# Side_Panel_f1.net
KiCad netlist of a schematic drawn in EAGLE
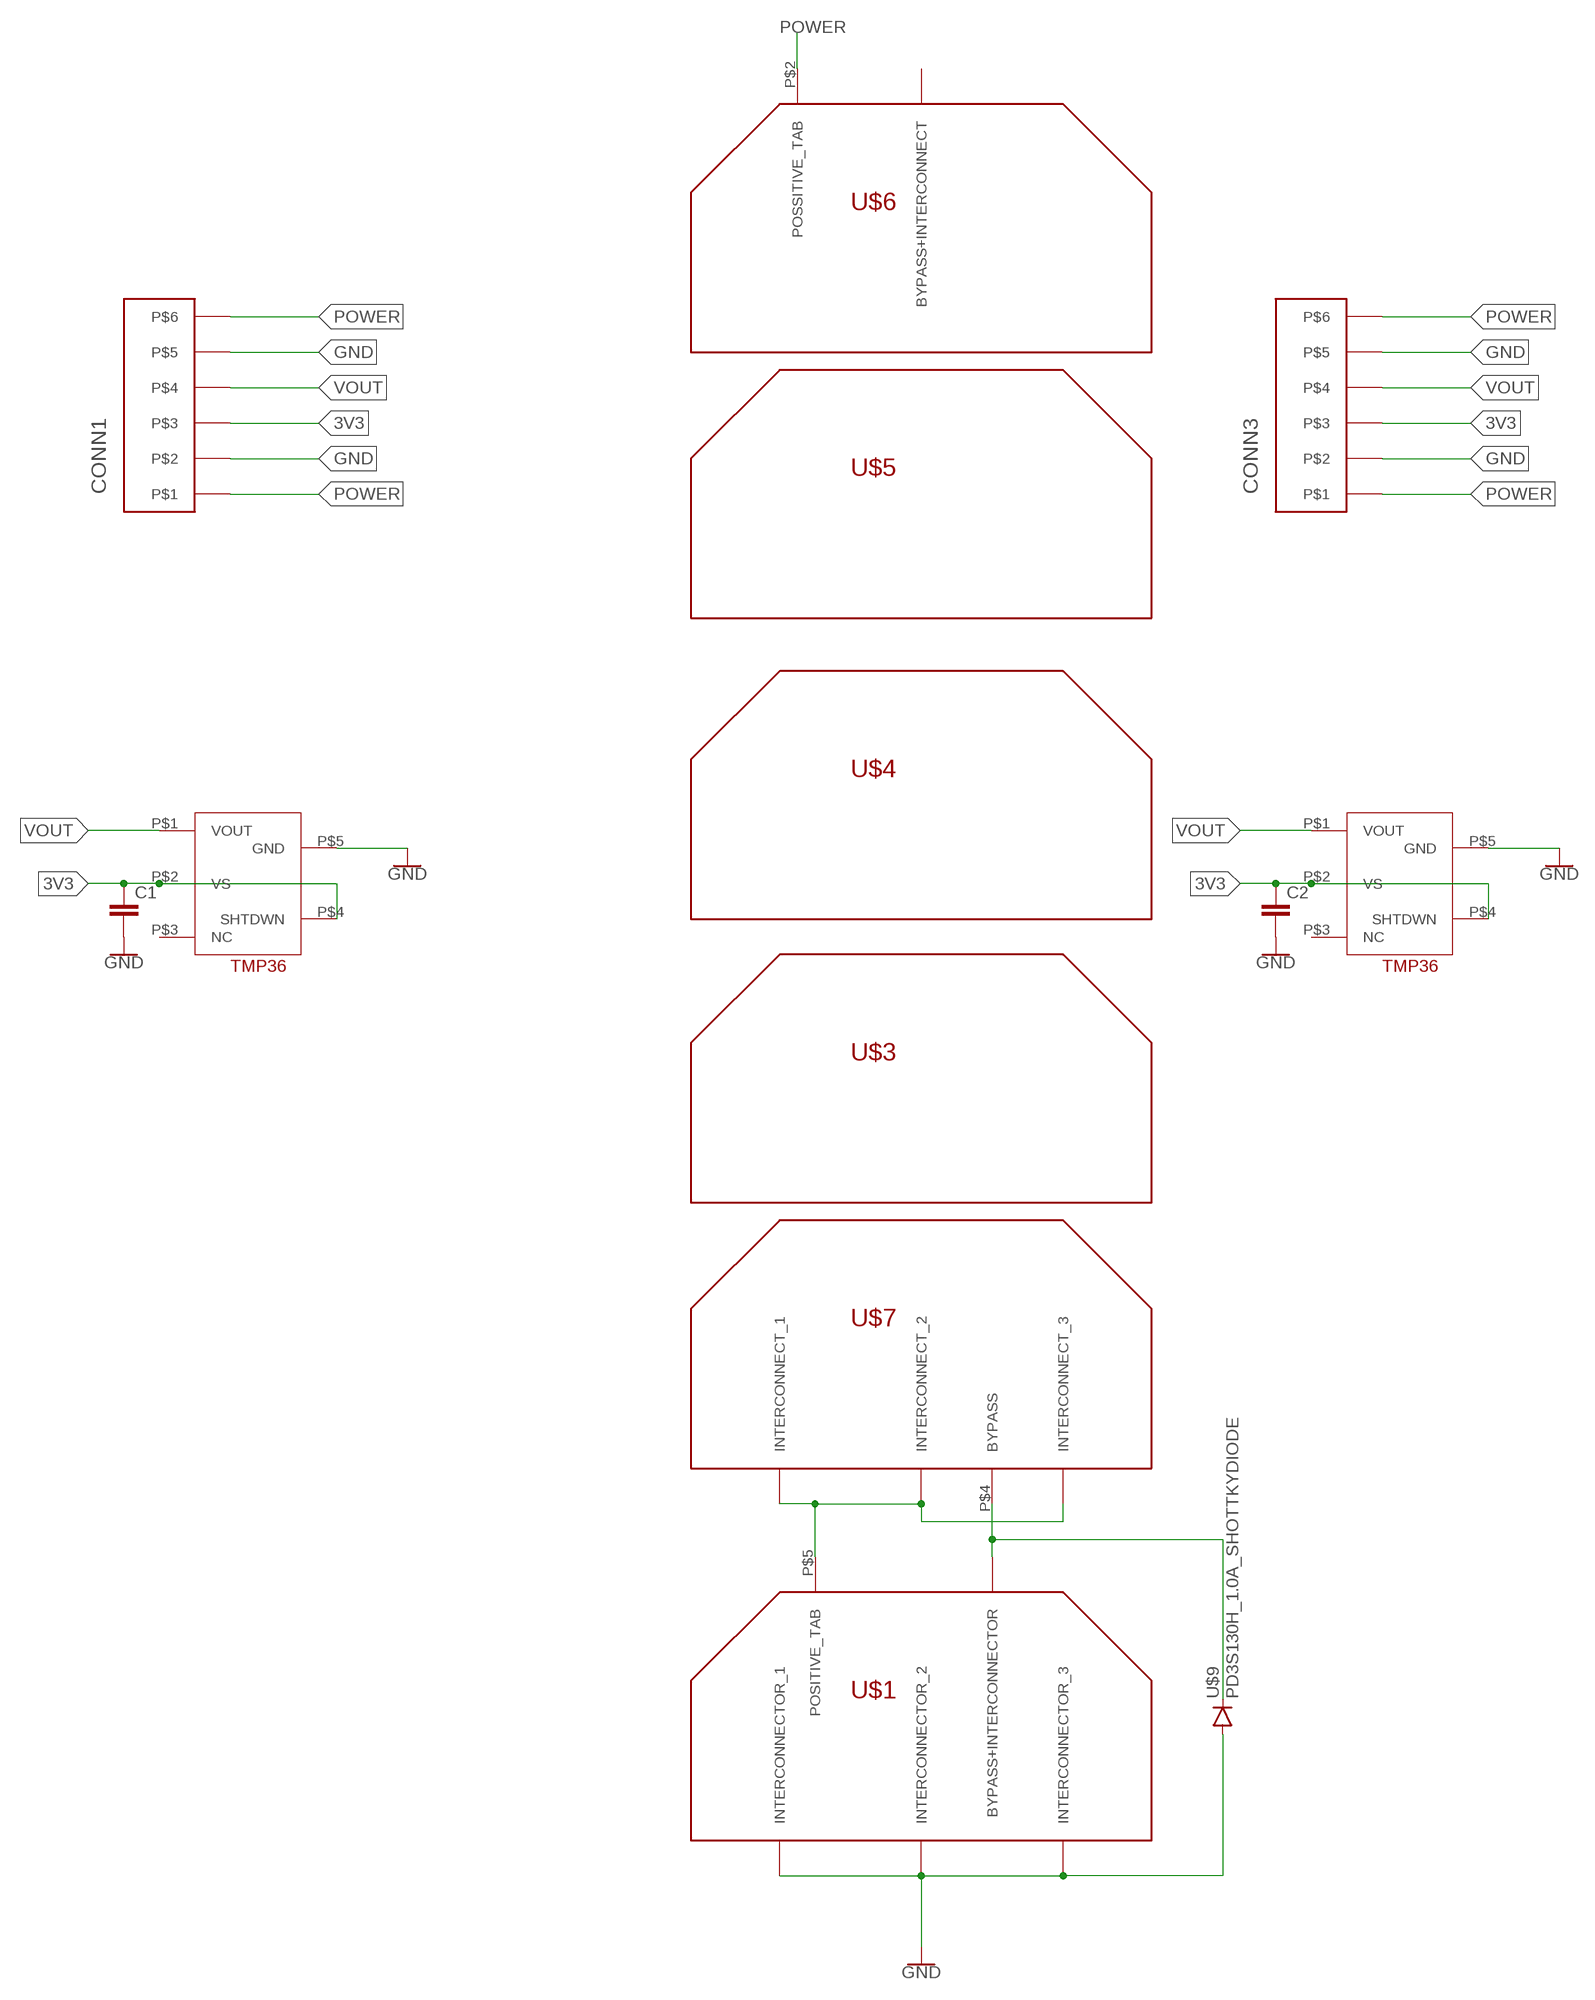
[diagram p0: schematic, sheet 1]

(export (version "E")
  (design (tool "Eeschema 10.0.6"))
  (components
    (comp (ref "C1")
      (value "CAPACITOR0805")
      (footprint "eagle-import:0805")
      (libsource (lib "eagle-import") (part "CAPACITOR0805"))
    )
    (comp (ref "C2")
      (value "CAPACITOR0805")
      (footprint "eagle-import:0805")
      (libsource (lib "eagle-import") (part "CAPACITOR0805"))
    )
    (comp (ref "CONN1")
      (value "PICOLOCK_6PICOLOCK_6")
      (footprint "eagle-import:PICOLOCK_6")
      (libsource (lib "eagle-import") (part "PICOLOCK_6PICOLOCK_6"))
    )
    (comp (ref "CONN3")
      (value "PICOLOCK_6PICOLOCK_6")
      (footprint "eagle-import:PICOLOCK_6")
      (libsource (lib "eagle-import") (part "PICOLOCK_6PICOLOCK_6"))
    )
    (comp (ref "U$1")
      (value "SOLAR_CELL_STAND-ALONE")
      (footprint "eagle-import:SOLAR_CELL_STAND-ALONE")
      (libsource (lib "eagle-import") (part "SOLAR_CELL_STAND-ALONE"))
    )
    (comp (ref "U$2")
      (value "TMP36")
      (footprint "eagle-import:SOT-23-5")
      (libsource (lib "eagle-import") (part "TMP36"))
    )
    (comp (ref "U$3")
      (value "SOALAR_CELL_OUTLINE")
      (footprint "eagle-import:SOLAR_CELL_OUTLINE")
      (libsource (lib "eagle-import") (part "SOALAR_CELL_OUTLINE"))
    )
    (comp (ref "U$4")
      (value "SOALAR_CELL_OUTLINE")
      (footprint "eagle-import:SOLAR_CELL_OUTLINE")
      (libsource (lib "eagle-import") (part "SOALAR_CELL_OUTLINE"))
    )
    (comp (ref "U$5")
      (value "SOALAR_CELL_OUTLINE")
      (footprint "eagle-import:SOLAR_CELL_OUTLINE")
      (libsource (lib "eagle-import") (part "SOALAR_CELL_OUTLINE"))
    )
    (comp (ref "U$6")
      (value "SOLAR_CELL_TOP")
      (footprint "eagle-import:SOLAR_CELL_TOP_SHORT-PAD")
      (libsource (lib "eagle-import") (part "SOLAR_CELL_TOP"))
    )
    (comp (ref "U$7")
      (value "SOLAR_CELL_BOTTOM+BYPASS")
      (footprint "eagle-import:SOLAR_CELL_BOTTOM+BYPASS")
      (libsource (lib "eagle-import") (part "SOLAR_CELL_BOTTOM+BYPASS"))
    )
    (comp (ref "U$8")
      (value "TMP36")
      (footprint "eagle-import:SOT-23-5")
      (libsource (lib "eagle-import") (part "TMP36"))
    )
    (comp (ref "U$9")
      (value "PD3S130H_1.0A_SHOTTKYDIODE")
      (footprint "eagle-import:POWERDI_323")
      (libsource (lib "eagle-import") (part "PD3S130H_1.0A_SHOTTKYDIODE"))
    )
  )
  (nets
    (net (code "1") (name "3V3") (class "Default")
      (node (ref "C1") (pin "1") (pinfunction "1_1") (pintype "passive"))
      (node (ref "C2") (pin "1") (pinfunction "1_1") (pintype "passive"))
      (node (ref "CONN1") (pin "P$3") (pinfunction "P$3_P$3") (pintype "bidirectional"))
      (node (ref "CONN3") (pin "P$3") (pinfunction "P$3_P$3") (pintype "bidirectional"))
      (node (ref "U$2") (pin "P$2") (pinfunction "VS_P$2") (pintype "bidirectional"))
      (node (ref "U$2") (pin "P$4") (pinfunction "SHTDWN_P$4") (pintype "bidirectional"))
      (node (ref "U$8") (pin "P$2") (pinfunction "VS_P$2") (pintype "bidirectional"))
      (node (ref "U$8") (pin "P$4") (pinfunction "SHTDWN_P$4") (pintype "bidirectional"))
    )
    (net (code "2") (name "GND") (class "Default")
      (node (ref "C1") (pin "2") (pinfunction "2_2") (pintype "passive"))
      (node (ref "C2") (pin "2") (pinfunction "2_2") (pintype "passive"))
      (node (ref "CONN1") (pin "P$2") (pinfunction "P$2_P$2") (pintype "bidirectional"))
      (node (ref "CONN1") (pin "P$5") (pinfunction "P$5_P$5") (pintype "bidirectional"))
      (node (ref "CONN3") (pin "P$2") (pinfunction "P$2_P$2") (pintype "bidirectional"))
      (node (ref "CONN3") (pin "P$5") (pinfunction "P$5_P$5") (pintype "bidirectional"))
      (node (ref "U$1") (pin "P$1") (pinfunction "INTERCONNECTOR_1_P$1") (pintype "bidirectional"))
      (node (ref "U$1") (pin "P$2") (pinfunction "INTERCONNECTOR_2_P$2") (pintype "bidirectional"))
      (node (ref "U$1") (pin "P$3") (pinfunction "INTERCONNECTOR_3_P$3") (pintype "bidirectional"))
      (node (ref "U$2") (pin "P$5") (pinfunction "GND_P$5") (pintype "bidirectional"))
      (node (ref "U$8") (pin "P$5") (pinfunction "GND_P$5") (pintype "bidirectional"))
      (node (ref "U$9") (pin "P$2") (pinfunction "A_P$2") (pintype "passive"))
    )
    (net (code "3") (name "Net-(U$1-BYPASS+INTERCONNECTOR)") (class "Default")
      (node (ref "U$1") (pin "P$4") (pinfunction "BYPASS+INTERCONNECTOR_P$4") (pintype "bidirectional"))
      (node (ref "U$7") (pin "P$4") (pinfunction "BYPASS_P$4") (pintype "bidirectional"))
      (node (ref "U$9") (pin "P$1") (pinfunction "C_P$1") (pintype "passive"))
    )
    (net (code "4") (name "Net-(U$1-POSITIVE_TAB)") (class "Default")
      (node (ref "U$1") (pin "P$5") (pinfunction "POSITIVE_TAB_P$5") (pintype "bidirectional"))
      (node (ref "U$7") (pin "P$1") (pinfunction "INTERCONNECT_1_P$1") (pintype "bidirectional"))
      (node (ref "U$7") (pin "P$2") (pinfunction "INTERCONNECT_2_P$2") (pintype "bidirectional"))
      (node (ref "U$7") (pin "P$3") (pinfunction "INTERCONNECT_3_P$3") (pintype "bidirectional"))
    )
    (net (code "5") (name "POWER") (class "Default")
      (node (ref "CONN1") (pin "P$1") (pinfunction "P$1_P$1") (pintype "bidirectional"))
      (node (ref "CONN1") (pin "P$6") (pinfunction "P$6_P$6") (pintype "bidirectional"))
      (node (ref "CONN3") (pin "P$1") (pinfunction "P$1_P$1") (pintype "bidirectional"))
      (node (ref "CONN3") (pin "P$6") (pinfunction "P$6_P$6") (pintype "bidirectional"))
      (node (ref "U$6") (pin "P$2") (pinfunction "POSSITIVE_TAB_P$2") (pintype "bidirectional"))
    )
    (net (code "6") (name "VOUT") (class "Default")
      (node (ref "CONN1") (pin "P$4") (pinfunction "P$4_P$4") (pintype "bidirectional"))
      (node (ref "CONN3") (pin "P$4") (pinfunction "P$4_P$4") (pintype "bidirectional"))
      (node (ref "U$2") (pin "P$1") (pinfunction "VOUT_P$1") (pintype "bidirectional"))
      (node (ref "U$8") (pin "P$1") (pinfunction "VOUT_P$1") (pintype "bidirectional"))
    )
    (net (code "7") (name "unconnected-(U$2-NC-PadP$3)") (class "Default")
      (node (ref "U$2") (pin "P$3") (pinfunction "NC_P$3") (pintype "bidirectional"))
    )
    (net (code "8") (name "unconnected-(U$6-BYPASS+INTERCONNECT-PadP$1)") (class "Default")
      (node (ref "U$6") (pin "P$1") (pinfunction "BYPASS+INTERCONNECT_P$1") (pintype "bidirectional"))
    )
    (net (code "9") (name "unconnected-(U$8-NC-PadP$3)") (class "Default")
      (node (ref "U$8") (pin "P$3") (pinfunction "NC_P$3") (pintype "bidirectional"))
    )
  )
)
